# oLoRa-part-Geiger.net
KiCad netlist of a schematic drawn in EasyEDA
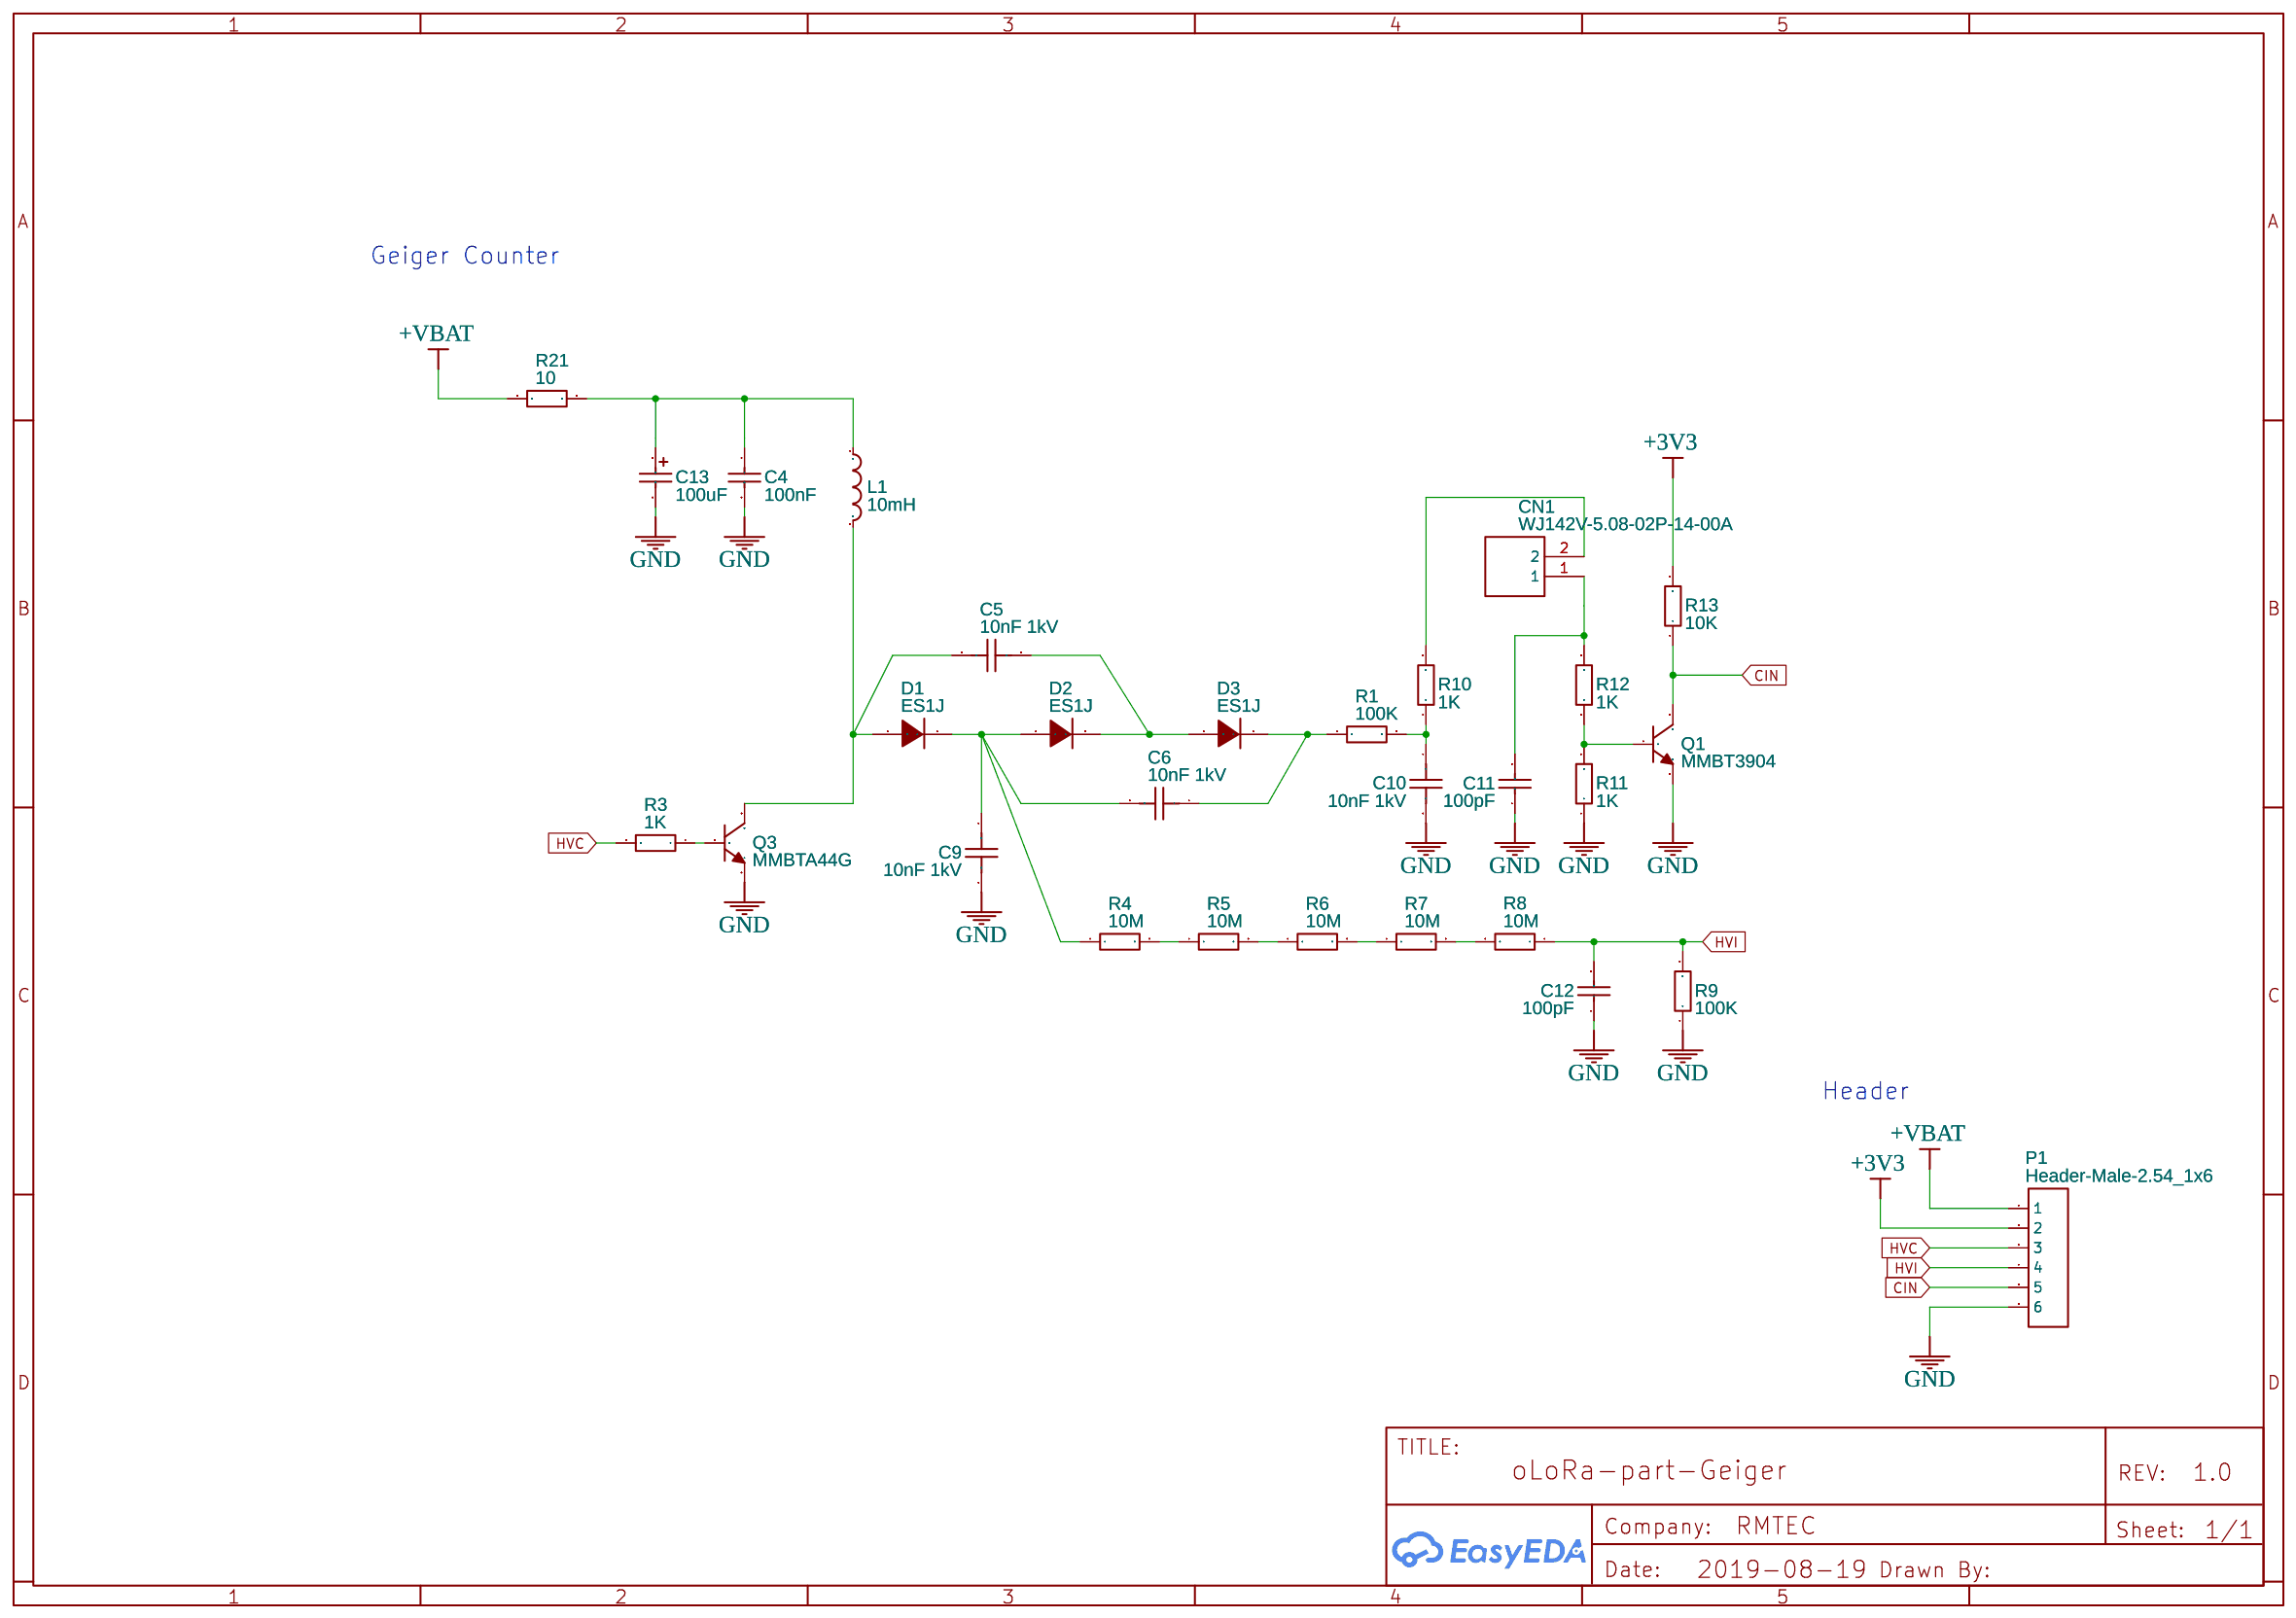
[diagram p0: schematic sheet]

(export (version "E")
  (design (tool "Eeschema 10.0.6"))
  (components
    (comp (ref "C4")
      (value "100nF")
      (fields
        (field (name "BOM_Manufacturer Part") "0603B104K500NT")
        (field (name "BOM_Supplier Part") "C30926")
      )
      (libsource (lib "") (part "0603B104K500NT"))
    )
    (comp (ref "C5")
      (value "10nF 1kV")
      (fields
        (field (name "BOM_Manufacturer Part") "1206B103K102CT")
        (field (name "BOM_Supplier Part") "C303948")
      )
      (libsource (lib "") (part "1206B103K102CT_1"))
    )
    (comp (ref "C6")
      (value "10nF 1kV")
      (fields
        (field (name "BOM_Manufacturer Part") "1206B103K102CT")
        (field (name "BOM_Supplier Part") "C303948")
      )
      (libsource (lib "") (part "1206B103K102CT_1"))
    )
    (comp (ref "C9")
      (value "10nF 1kV")
      (fields
        (field (name "BOM_Manufacturer Part") "1206B103K102CT")
        (field (name "BOM_Supplier Part") "C303948")
      )
      (libsource (lib "") (part "1206B103K102CT"))
    )
    (comp (ref "C10")
      (value "10nF 1kV")
      (fields
        (field (name "BOM_Manufacturer Part") "1206B103K102CT")
        (field (name "BOM_Supplier Part") "C303948")
      )
      (libsource (lib "") (part "1206B103K102CT"))
    )
    (comp (ref "C11")
      (value "100pF")
      (fields
        (field (name "BOM_Manufacturer Part") "0603CG101J500NT")
        (field (name "BOM_Supplier Part") "C1635")
      )
      (libsource (lib "") (part "0603CG101J500NT"))
    )
    (comp (ref "C12")
      (value "100pF")
      (fields
        (field (name "BOM_Manufacturer Part") "0603CG101J500NT")
        (field (name "BOM_Supplier Part") "C1635")
      )
      (libsource (lib "") (part "0603CG101J500NT"))
    )
    (comp (ref "C13")
      (value "100uF")
      (fields
        (field (name "BOM_Manufacturer Part") "TAJB107M010RNJ")
        (field (name "BOM_Supplier Part") "C7196")
      )
      (libsource (lib "") (part "TAJB107M010RNJ"))
    )
    (comp (ref "CN1")
      (value "WJ142V-5.08-02P-14-00A")
      (fields (field (name "BOM_Supplier Part") "C153288"))
      (libsource (lib "") (part "Unknown_770_280"))
    )
    (comp (ref "D1")
      (value "ES1J")
      (fields (field (name "BOM_Supplier Part") "C232830"))
      (libsource (lib "") (part "Unknown_455_365"))
    )
    (comp (ref "D2")
      (value "ES1J")
      (fields (field (name "BOM_Supplier Part") "C232830"))
      (libsource (lib "") (part "Unknown_530_365"))
    )
    (comp (ref "D3")
      (value "ES1J")
      (fields (field (name "BOM_Supplier Part") "C232830"))
      (libsource (lib "") (part "Unknown_615_365"))
    )
    (comp (ref "L1")
      (value "10mH")
      (fields
        (field (name "BOM_Manufacturer Part") "FNR5040S103MT")
        (field (name "BOM_Supplier Part") "C167995")
      )
      (libsource (lib "") (part "FNR5040S103MT"))
    )
    (comp (ref "P1")
      (value "Header-Male-2.54_1x6")
      (fields (field (name "BOM_Supplier Part") "C37208"))
      (libsource (lib "") (part "Unknown_1025_630"))
    )
    (comp (ref "Q1")
      (value "MMBT3904")
      (fields (field (name "BOM_Supplier Part") "C111113"))
      (libsource (lib "") (part "Unknown_830_370"))
    )
    (comp (ref "Q3")
      (value "MMBTA44G")
      (fields
        (field (name "BOM_Manufacturer Part") "MMBTA44G-AE3-R")
        (field (name "BOM_Supplier Part") "C84882")
      )
      (libsource (lib "") (part "Unknown_360_420"))
    )
    (comp (ref "R1")
      (value "100K")
      (fields
        (field (name "BOM_Manufacturer Part") "RC0603FR-07100KL")
        (field (name "BOM_Supplier Part") "C14675")
      )
      (libsource (lib "") (part "RC0603FR-07100KL_1"))
    )
    (comp (ref "R3")
      (value "1K")
      (fields
        (field (name "BOM_Manufacturer Part") "RC0603FR-071KL")
        (field (name "BOM_Supplier Part") "C22548")
      )
      (libsource (lib "") (part "RC0603FR-071KL_1"))
    )
    (comp (ref "R4")
      (value "10M")
      (fields
        (field (name "BOM_Manufacturer Part") "RTT031005FTP")
        (field (name "BOM_Supplier Part") "C103202")
      )
      (libsource (lib "") (part "RTT031005FTP"))
    )
    (comp (ref "R5")
      (value "10M")
      (fields
        (field (name "BOM_Manufacturer Part") "RTT031005FTP")
        (field (name "BOM_Supplier Part") "C103202")
      )
      (libsource (lib "") (part "RTT031005FTP"))
    )
    (comp (ref "R6")
      (value "10M")
      (fields
        (field (name "BOM_Manufacturer Part") "RTT031005FTP")
        (field (name "BOM_Supplier Part") "C103202")
      )
      (libsource (lib "") (part "RTT031005FTP"))
    )
    (comp (ref "R7")
      (value "10M")
      (fields
        (field (name "BOM_Manufacturer Part") "RTT031005FTP")
        (field (name "BOM_Supplier Part") "C103202")
      )
      (libsource (lib "") (part "RTT031005FTP"))
    )
    (comp (ref "R8")
      (value "10M")
      (fields
        (field (name "BOM_Manufacturer Part") "RTT031005FTP")
        (field (name "BOM_Supplier Part") "C103202")
      )
      (libsource (lib "") (part "RTT031005FTP_1"))
    )
    (comp (ref "R9")
      (value "100K")
      (fields
        (field (name "BOM_Manufacturer Part") "RC0603FR-07100KL")
        (field (name "BOM_Supplier Part") "C14675")
      )
      (libsource (lib "") (part "RC0603FR-07100KL"))
    )
    (comp (ref "R10")
      (value "1K")
      (fields
        (field (name "BOM_Manufacturer Part") "RC0603FR-071KL")
        (field (name "BOM_Supplier Part") "C22548")
      )
      (libsource (lib "") (part "RC0603FR-071KL"))
    )
    (comp (ref "R11")
      (value "1K")
      (fields
        (field (name "BOM_Manufacturer Part") "RC0603FR-071KL")
        (field (name "BOM_Supplier Part") "C22548")
      )
      (libsource (lib "") (part "RC0603FR-071KL"))
    )
    (comp (ref "R12")
      (value "1K")
      (fields
        (field (name "BOM_Manufacturer Part") "RC0603FR-071KL")
        (field (name "BOM_Supplier Part") "C22548")
      )
      (libsource (lib "") (part "RC0603FR-071KL"))
    )
    (comp (ref "R13")
      (value "10K")
      (fields
        (field (name "BOM_Manufacturer Part") "0603WAF1002T5E")
        (field (name "BOM_Supplier Part") "C25804")
      )
      (libsource (lib "") (part "0603WAF1002T5E"))
    )
    (comp (ref "R21")
      (value "10")
      (fields
        (field (name "BOM_Manufacturer Part") "RC0805FR-0710RL")
        (field (name "BOM_Supplier Part") "C96347")
      )
      (libsource (lib "") (part "RC0805FR-0710RL"))
    )
  )
  (nets
    (net (code "1") (name "+3V3") (class "Default")
      (node (ref "P1") (pin "2") (pinfunction "2_2") (pintype "input"))
      (node (ref "R13") (pin "2") (pinfunction "2_2") (pintype "input"))
    )
    (net (code "2") (name "+VBAT") (class "Default")
      (node (ref "P1") (pin "1") (pinfunction "1_1") (pintype "input"))
      (node (ref "R21") (pin "1") (pinfunction "1_1") (pintype "input"))
    )
    (net (code "3") (name "CIN") (class "Default")
      (node (ref "P1") (pin "5") (pinfunction "5_5") (pintype "input"))
      (node (ref "Q1") (pin "3") (pinfunction "3_3") (pintype "input"))
      (node (ref "R13") (pin "1") (pinfunction "1_1") (pintype "input"))
    )
    (net (code "4") (name "GND") (class "Default")
      (node (ref "C10") (pin "2") (pinfunction "2_2") (pintype "unspecified"))
      (node (ref "C11") (pin "1") (pinfunction "1_1") (pintype "input"))
      (node (ref "C12") (pin "1") (pinfunction "1_1") (pintype "input"))
      (node (ref "C13") (pin "2") (pinfunction "2_2") (pintype "input"))
      (node (ref "C4") (pin "2") (pinfunction "2_2") (pintype "input"))
      (node (ref "C9") (pin "2") (pinfunction "2_2") (pintype "unspecified"))
      (node (ref "P1") (pin "6") (pinfunction "6_6") (pintype "input"))
      (node (ref "Q1") (pin "2") (pinfunction "2_2") (pintype "input"))
      (node (ref "Q3") (pin "2") (pinfunction "E_2") (pintype "unspecified"))
      (node (ref "R11") (pin "1") (pinfunction "1_1") (pintype "input"))
      (node (ref "R9") (pin "1") (pinfunction "1_1") (pintype "unspecified"))
    )
    (net (code "5") (name "HVC") (class "Default")
      (node (ref "P1") (pin "3") (pinfunction "3_3") (pintype "input"))
      (node (ref "R3") (pin "2") (pinfunction "2_2") (pintype "input"))
    )
    (net (code "6") (name "HVI") (class "Default")
      (node (ref "C12") (pin "2") (pinfunction "2_2") (pintype "input"))
      (node (ref "P1") (pin "4") (pinfunction "4_4") (pintype "input"))
      (node (ref "R8") (pin "1") (pinfunction "1_1") (pintype "input"))
      (node (ref "R9") (pin "2") (pinfunction "2_2") (pintype "unspecified"))
    )
    (net (code "7") (name "Net-(C10-Pad1)") (class "Default")
      (node (ref "C10") (pin "1") (pinfunction "1_1") (pintype "unspecified"))
      (node (ref "R1") (pin "2") (pinfunction "2_2") (pintype "unspecified"))
      (node (ref "R10") (pin "1") (pinfunction "1_1") (pintype "input"))
    )
    (net (code "8") (name "Net-(C11-Pad2)") (class "Default")
      (node (ref "C11") (pin "2") (pinfunction "2_2") (pintype "input"))
      (node (ref "CN1") (pin "1") (pinfunction "1_1") (pintype "unspecified"))
      (node (ref "R12") (pin "2") (pinfunction "2_2") (pintype "input"))
    )
    (net (code "9") (name "Net-(C13-Pad1)") (class "Default")
      (node (ref "C13") (pin "1") (pinfunction "1_1") (pintype "input"))
      (node (ref "C4") (pin "1") (pinfunction "1_1") (pintype "input"))
      (node (ref "L1") (pin "1") (pinfunction "1_1") (pintype "unspecified"))
      (node (ref "R21") (pin "2") (pinfunction "2_2") (pintype "input"))
    )
    (net (code "10") (name "Net-(CN1-Pad2)") (class "Default")
      (node (ref "CN1") (pin "2") (pinfunction "2_2") (pintype "unspecified"))
      (node (ref "R10") (pin "2") (pinfunction "2_2") (pintype "input"))
    )
    (net (code "11") (name "Net-(D1-A)") (class "Default")
      (node (ref "C5") (pin "2") (pinfunction "2_2") (pintype "unspecified"))
      (node (ref "D1") (pin "1") (pinfunction "A_1") (pintype "unspecified"))
      (node (ref "L1") (pin "2") (pinfunction "2_2") (pintype "unspecified"))
      (node (ref "Q3") (pin "3") (pinfunction "C_3") (pintype "unspecified"))
    )
    (net (code "12") (name "Net-(D1-K)") (class "Default")
      (node (ref "C6") (pin "2") (pinfunction "2_2") (pintype "unspecified"))
      (node (ref "C9") (pin "1") (pinfunction "1_1") (pintype "unspecified"))
      (node (ref "D1") (pin "2") (pinfunction "K_2") (pintype "unspecified"))
      (node (ref "D2") (pin "1") (pinfunction "A_1") (pintype "unspecified"))
      (node (ref "R4") (pin "1") (pinfunction "1_1") (pintype "input"))
    )
    (net (code "13") (name "Net-(D2-K)") (class "Default")
      (node (ref "C5") (pin "1") (pinfunction "1_1") (pintype "unspecified"))
      (node (ref "D2") (pin "2") (pinfunction "K_2") (pintype "unspecified"))
      (node (ref "D3") (pin "1") (pinfunction "A_1") (pintype "unspecified"))
    )
    (net (code "14") (name "Net-(D3-K)") (class "Default")
      (node (ref "C6") (pin "1") (pinfunction "1_1") (pintype "unspecified"))
      (node (ref "D3") (pin "2") (pinfunction "K_2") (pintype "unspecified"))
      (node (ref "R1") (pin "1") (pinfunction "1_1") (pintype "unspecified"))
    )
    (net (code "15") (name "Net-(Q1-Pad1)") (class "Default")
      (node (ref "Q1") (pin "1") (pinfunction "1_1") (pintype "input"))
      (node (ref "R11") (pin "2") (pinfunction "2_2") (pintype "input"))
      (node (ref "R12") (pin "1") (pinfunction "1_1") (pintype "input"))
    )
    (net (code "16") (name "Net-(Q3-B)") (class "Default")
      (node (ref "Q3") (pin "1") (pinfunction "B_1") (pintype "unspecified"))
      (node (ref "R3") (pin "1") (pinfunction "1_1") (pintype "input"))
    )
    (net (code "17") (name "Net-(R4-Pad2)") (class "Default")
      (node (ref "R4") (pin "2") (pinfunction "2_2") (pintype "input"))
      (node (ref "R5") (pin "1") (pinfunction "1_1") (pintype "input"))
    )
    (net (code "18") (name "Net-(R5-Pad2)") (class "Default")
      (node (ref "R5") (pin "2") (pinfunction "2_2") (pintype "input"))
      (node (ref "R6") (pin "1") (pinfunction "1_1") (pintype "input"))
    )
    (net (code "19") (name "Net-(R6-Pad2)") (class "Default")
      (node (ref "R6") (pin "2") (pinfunction "2_2") (pintype "input"))
      (node (ref "R7") (pin "1") (pinfunction "1_1") (pintype "input"))
    )
    (net (code "20") (name "Net-(R7-Pad2)") (class "Default")
      (node (ref "R7") (pin "2") (pinfunction "2_2") (pintype "input"))
      (node (ref "R8") (pin "2") (pinfunction "2_2") (pintype "input"))
    )
  )
)
